# Sheet2.net
KiCad netlist of a schematic drawn in Altium Designer
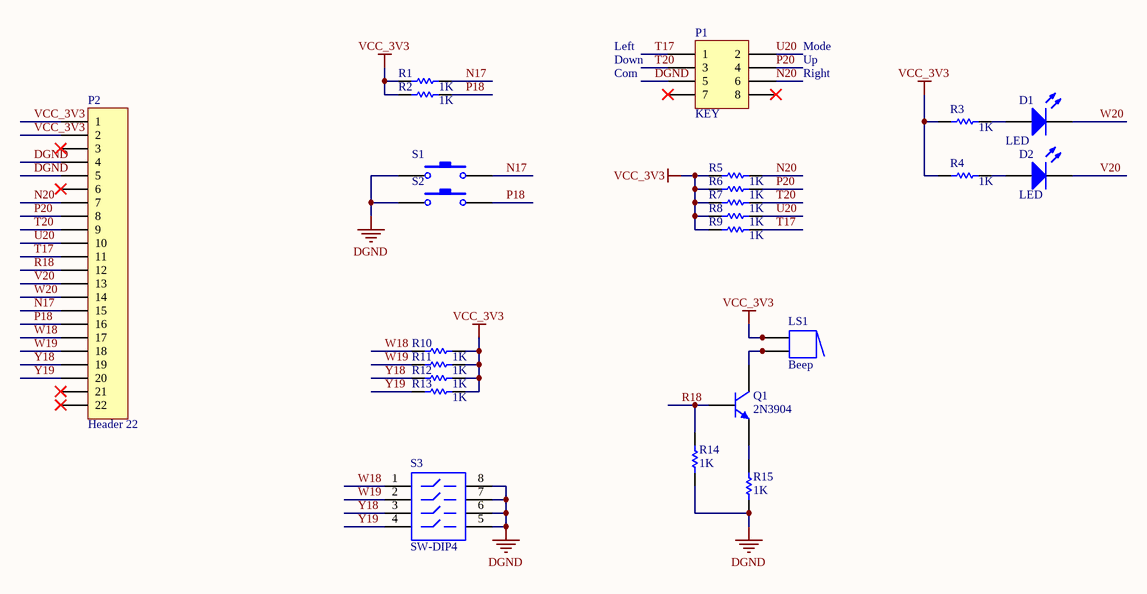
[diagram p0: Sheet2.SchDoc]

(export (version "E")
  (design (tool "Eeschema 10.0.6"))
  (components
    (comp (ref "D1")
      (value "LED")
      (footprint "LED0805绿")
      (description "Typical INFRARED GaAs LED")
      (fields (field (name "PUBLISHER") "Altium Limited"))
      (libsource (lib "Miscellaneous Devices") (part "LED0"))
    )
    (comp (ref "D2")
      (value "LED")
      (footprint "LED0805绿")
      (description "Typical INFRARED GaAs LED")
      (fields (field (name "PUBLISHER") "Altium Limited"))
      (libsource (lib "Miscellaneous Devices") (part "LED0"))
    )
    (comp (ref "LS1")
      (value "Beep")
      (footprint "蜂鸣器")
      (description "Magnetic Transducer Buzzer")
      (fields (field (name "PUBLISHER") "Altium Limited"))
      (libsource (lib "Miscellaneous Devices") (part "Buzzer"))
    )
    (comp (ref "P1")
      (value "KEY")
      (footprint "贴片5向按键")
      (description "Header, 4-Pin, Dual row")
      (fields (field (name "PUBLISHER") "Altium Limited"))
      (libsource (lib "Miscellaneous Connectors") (part "Header 4X2"))
    )
    (comp (ref "P2")
      (value "Header 22")
      (footprint "FPC20Pin")
      (description "Header, 22-Pin")
      (fields (field (name "PUBLISHER") "Altium Limited"))
      (libsource (lib "Miscellaneous Connectors") (part "Header 22"))
    )
    (comp (ref "Q1")
      (value "2N3904")
      (footprint "SOT23")
      (description "NPN General Purpose Amplifier")
      (fields (field (name "PUBLISHER") "Altium Limited"))
      (libsource (lib "Miscellaneous Devices") (part "2N3904"))
    )
    (comp (ref "R1")
      (value "1K")
      (footprint "R0805")
      (description "Resistor")
      (fields (field (name "Comment") "Res1") (field (name "PUBLISHER") "Altium Limited"))
      (libsource (lib "Miscellaneous Devices") (part "Res1"))
    )
    (comp (ref "R2")
      (value "1K")
      (footprint "R0805")
      (description "Resistor")
      (fields (field (name "Comment") "Res1") (field (name "PUBLISHER") "Altium Limited"))
      (libsource (lib "Miscellaneous Devices") (part "Res1"))
    )
    (comp (ref "R3")
      (value "1K")
      (footprint "R0805")
      (description "Resistor")
      (fields (field (name "Comment") "Res1") (field (name "PUBLISHER") "Altium Limited"))
      (libsource (lib "Miscellaneous Devices") (part "Res1"))
    )
    (comp (ref "R4")
      (value "1K")
      (footprint "R0805")
      (description "Resistor")
      (fields (field (name "Comment") "Res1") (field (name "PUBLISHER") "Altium Limited"))
      (libsource (lib "Miscellaneous Devices") (part "Res1"))
    )
    (comp (ref "R5")
      (value "1K")
      (footprint "R0805")
      (description "Resistor")
      (fields (field (name "Comment") "Res1") (field (name "PUBLISHER") "Altium Limited"))
      (libsource (lib "Miscellaneous Devices") (part "Res1"))
    )
    (comp (ref "R6")
      (value "1K")
      (footprint "R0805")
      (description "Resistor")
      (fields (field (name "Comment") "Res1") (field (name "PUBLISHER") "Altium Limited"))
      (libsource (lib "Miscellaneous Devices") (part "Res1"))
    )
    (comp (ref "R7")
      (value "1K")
      (footprint "R0805")
      (description "Resistor")
      (fields (field (name "Comment") "Res1") (field (name "PUBLISHER") "Altium Limited"))
      (libsource (lib "Miscellaneous Devices") (part "Res1"))
    )
    (comp (ref "R8")
      (value "1K")
      (footprint "R0805")
      (description "Resistor")
      (fields (field (name "Comment") "Res1") (field (name "PUBLISHER") "Altium Limited"))
      (libsource (lib "Miscellaneous Devices") (part "Res1"))
    )
    (comp (ref "R9")
      (value "1K")
      (footprint "R0805")
      (description "Resistor")
      (fields (field (name "Comment") "Res1") (field (name "PUBLISHER") "Altium Limited"))
      (libsource (lib "Miscellaneous Devices") (part "Res1"))
    )
    (comp (ref "R10")
      (value "1K")
      (footprint "R0805")
      (description "Resistor")
      (fields (field (name "Comment") "Res1") (field (name "PUBLISHER") "Altium Limited"))
      (libsource (lib "Miscellaneous Devices") (part "Res1"))
    )
    (comp (ref "R11")
      (value "1K")
      (footprint "R0805")
      (description "Resistor")
      (fields (field (name "Comment") "Res1") (field (name "PUBLISHER") "Altium Limited"))
      (libsource (lib "Miscellaneous Devices") (part "Res1"))
    )
    (comp (ref "R12")
      (value "1K")
      (footprint "R0805")
      (description "Resistor")
      (fields (field (name "Comment") "Res1") (field (name "PUBLISHER") "Altium Limited"))
      (libsource (lib "Miscellaneous Devices") (part "Res1"))
    )
    (comp (ref "R13")
      (value "1K")
      (footprint "R0805")
      (description "Resistor")
      (fields (field (name "Comment") "Res1") (field (name "PUBLISHER") "Altium Limited"))
      (libsource (lib "Miscellaneous Devices") (part "Res1"))
    )
    (comp (ref "R14")
      (value "1K")
      (footprint "R0805")
      (description "Resistor")
      (fields (field (name "Comment") "Res1") (field (name "PUBLISHER") "Altium Limited"))
      (libsource (lib "Miscellaneous Devices") (part "Res1"))
    )
    (comp (ref "R15")
      (value "1K")
      (footprint "R0805")
      (description "Resistor")
      (fields (field (name "Comment") "Res1") (field (name "PUBLISHER") "Altium Limited"))
      (libsource (lib "Miscellaneous Devices") (part "Res1"))
    )
    (comp (ref "S1")
      (value "SW-PB")
      (footprint "贴片按键")
      (description "Switch")
      (fields (field (name "PUBLISHER") "Altium Limited"))
      (libsource (lib "Miscellaneous Devices") (part "SW-PB"))
    )
    (comp (ref "S2")
      (value "SW-PB")
      (footprint "贴片按键")
      (description "Switch")
      (fields (field (name "PUBLISHER") "Altium Limited"))
      (libsource (lib "Miscellaneous Devices") (part "SW-PB"))
    )
    (comp (ref "S3")
      (value "SW-DIP4")
      (footprint "拨码开关4")
      (description "DIP Switch")
      (fields (field (name "PUBLISHER") "Altium Limited"))
      (libsource (lib "Miscellaneous Devices") (part "SW-DIP4"))
    )
  )
  (nets
    (net (code "1") (name "/N17") (class "Default")
      (node (ref "P2") (pin "15") (pinfunction "15_15") (pintype "passive"))
      (node (ref "R1") (pin "2") (pinfunction "2_2") (pintype "passive"))
      (node (ref "S1") (pin "2") (pinfunction "2_2") (pintype "passive"))
    )
    (net (code "2") (name "/N20") (class "Default")
      (node (ref "P1") (pin "6") (pinfunction "6_6") (pintype "passive"))
      (node (ref "P2") (pin "7") (pinfunction "7_7") (pintype "passive"))
      (node (ref "R5") (pin "2") (pinfunction "2_2") (pintype "passive"))
    )
    (net (code "3") (name "/P18") (class "Default")
      (node (ref "P2") (pin "16") (pinfunction "16_16") (pintype "passive"))
      (node (ref "R2") (pin "2") (pinfunction "2_2") (pintype "passive"))
      (node (ref "S2") (pin "2") (pinfunction "2_2") (pintype "passive"))
    )
    (net (code "4") (name "/P20") (class "Default")
      (node (ref "P1") (pin "4") (pinfunction "4_4") (pintype "passive"))
      (node (ref "P2") (pin "8") (pinfunction "8_8") (pintype "passive"))
      (node (ref "R6") (pin "2") (pinfunction "2_2") (pintype "passive"))
    )
    (net (code "5") (name "/R18") (class "Default")
      (node (ref "P2") (pin "12") (pinfunction "12_12") (pintype "passive"))
      (node (ref "Q1") (pin "B") (pinfunction "B_B") (pintype "passive"))
      (node (ref "R14") (pin "2") (pinfunction "2_2") (pintype "passive"))
    )
    (net (code "6") (name "/T17") (class "Default")
      (node (ref "P1") (pin "1") (pinfunction "1_1") (pintype "passive"))
      (node (ref "P2") (pin "11") (pinfunction "11_11") (pintype "passive"))
      (node (ref "R9") (pin "2") (pinfunction "2_2") (pintype "passive"))
    )
    (net (code "7") (name "/T20") (class "Default")
      (node (ref "P1") (pin "3") (pinfunction "3_3") (pintype "passive"))
      (node (ref "P2") (pin "9") (pinfunction "9_9") (pintype "passive"))
      (node (ref "R7") (pin "2") (pinfunction "2_2") (pintype "passive"))
    )
    (net (code "8") (name "/U20") (class "Default")
      (node (ref "P1") (pin "2") (pinfunction "2_2") (pintype "passive"))
      (node (ref "P2") (pin "10") (pinfunction "10_10") (pintype "passive"))
      (node (ref "R8") (pin "2") (pinfunction "2_2") (pintype "passive"))
    )
    (net (code "9") (name "/V20") (class "Default")
      (node (ref "D2") (pin "2") (pinfunction "K_2") (pintype "passive"))
      (node (ref "P2") (pin "13") (pinfunction "13_13") (pintype "passive"))
    )
    (net (code "10") (name "/W18") (class "Default")
      (node (ref "P2") (pin "17") (pinfunction "17_17") (pintype "passive"))
      (node (ref "R10") (pin "1") (pinfunction "1_1") (pintype "passive"))
      (node (ref "S3") (pin "1") (pinfunction "1_1") (pintype "passive"))
    )
    (net (code "11") (name "/W19") (class "Default")
      (node (ref "P2") (pin "18") (pinfunction "18_18") (pintype "passive"))
      (node (ref "R11") (pin "1") (pinfunction "1_1") (pintype "passive"))
      (node (ref "S3") (pin "2") (pinfunction "2_2") (pintype "passive"))
    )
    (net (code "12") (name "/W20") (class "Default")
      (node (ref "D1") (pin "2") (pinfunction "K_2") (pintype "passive"))
      (node (ref "P2") (pin "14") (pinfunction "14_14") (pintype "passive"))
    )
    (net (code "13") (name "/Y18") (class "Default")
      (node (ref "P2") (pin "19") (pinfunction "19_19") (pintype "passive"))
      (node (ref "R12") (pin "1") (pinfunction "1_1") (pintype "passive"))
      (node (ref "S3") (pin "3") (pinfunction "3_3") (pintype "passive"))
    )
    (net (code "14") (name "/Y19") (class "Default")
      (node (ref "P2") (pin "20") (pinfunction "20_20") (pintype "passive"))
      (node (ref "R13") (pin "1") (pinfunction "1_1") (pintype "passive"))
      (node (ref "S3") (pin "4") (pinfunction "4_4") (pintype "passive"))
    )
    (net (code "15") (name "DGND") (class "Default")
      (node (ref "P1") (pin "5") (pinfunction "5_5") (pintype "passive"))
      (node (ref "P2") (pin "4") (pinfunction "4_4") (pintype "passive"))
      (node (ref "P2") (pin "5") (pinfunction "5_5") (pintype "passive"))
      (node (ref "R14") (pin "1") (pinfunction "1_1") (pintype "passive"))
      (node (ref "R15") (pin "1") (pinfunction "1_1") (pintype "passive"))
      (node (ref "S1") (pin "1") (pinfunction "1_1") (pintype "passive"))
      (node (ref "S2") (pin "1") (pinfunction "1_1") (pintype "passive"))
      (node (ref "S3") (pin "5") (pinfunction "5_5") (pintype "passive"))
      (node (ref "S3") (pin "6") (pinfunction "6_6") (pintype "passive"))
      (node (ref "S3") (pin "7") (pinfunction "7_7") (pintype "passive"))
      (node (ref "S3") (pin "8") (pinfunction "8_8") (pintype "passive"))
    )
    (net (code "16") (name "Net-(D1-A)") (class "Default")
      (node (ref "D1") (pin "1") (pinfunction "A_1") (pintype "passive"))
      (node (ref "R3") (pin "2") (pinfunction "2_2") (pintype "passive"))
    )
    (net (code "17") (name "Net-(D2-A)") (class "Default")
      (node (ref "D2") (pin "1") (pinfunction "A_1") (pintype "passive"))
      (node (ref "R4") (pin "2") (pinfunction "2_2") (pintype "passive"))
    )
    (net (code "18") (name "Net-(LS1-Pad2)") (class "Default")
      (node (ref "LS1") (pin "2") (pinfunction "2_2") (pintype "passive"))
      (node (ref "Q1") (pin "C") (pinfunction "C_C") (pintype "passive"))
    )
    (net (code "19") (name "Net-(Q1-PadE)") (class "Default")
      (node (ref "Q1") (pin "E") (pinfunction "E_E") (pintype "passive"))
      (node (ref "R15") (pin "2") (pinfunction "2_2") (pintype "passive"))
    )
    (net (code "20") (name "VCC_3V3") (class "Default")
      (node (ref "LS1") (pin "1") (pinfunction "1_1") (pintype "passive"))
      (node (ref "LS1") (pin "1A") (pinfunction "1A_1A") (pintype "passive"))
      (node (ref "P2") (pin "1") (pinfunction "1_1") (pintype "passive"))
      (node (ref "P2") (pin "2") (pinfunction "2_2") (pintype "passive"))
      (node (ref "R1") (pin "1") (pinfunction "1_1") (pintype "passive"))
      (node (ref "R10") (pin "2") (pinfunction "2_2") (pintype "passive"))
      (node (ref "R11") (pin "2") (pinfunction "2_2") (pintype "passive"))
      (node (ref "R12") (pin "2") (pinfunction "2_2") (pintype "passive"))
      (node (ref "R13") (pin "2") (pinfunction "2_2") (pintype "passive"))
      (node (ref "R2") (pin "1") (pinfunction "1_1") (pintype "passive"))
      (node (ref "R3") (pin "1") (pinfunction "1_1") (pintype "passive"))
      (node (ref "R4") (pin "1") (pinfunction "1_1") (pintype "passive"))
      (node (ref "R5") (pin "1") (pinfunction "1_1") (pintype "passive"))
      (node (ref "R6") (pin "1") (pinfunction "1_1") (pintype "passive"))
      (node (ref "R7") (pin "1") (pinfunction "1_1") (pintype "passive"))
      (node (ref "R8") (pin "1") (pinfunction "1_1") (pintype "passive"))
      (node (ref "R9") (pin "1") (pinfunction "1_1") (pintype "passive"))
    )
    (net (code "21") (name "unconnected-(P1-Pad7)") (class "Default")
      (node (ref "P1") (pin "7") (pinfunction "7_7") (pintype "passive+no_connect"))
    )
    (net (code "22") (name "unconnected-(P1-Pad8)") (class "Default")
      (node (ref "P1") (pin "8") (pinfunction "8_8") (pintype "passive+no_connect"))
    )
    (net (code "23") (name "unconnected-(P2-Pad3)") (class "Default")
      (node (ref "P2") (pin "3") (pinfunction "3_3") (pintype "passive+no_connect"))
    )
    (net (code "24") (name "unconnected-(P2-Pad6)") (class "Default")
      (node (ref "P2") (pin "6") (pinfunction "6_6") (pintype "passive+no_connect"))
    )
    (net (code "25") (name "unconnected-(P2-Pad21)") (class "Default")
      (node (ref "P2") (pin "21") (pinfunction "21_21") (pintype "passive+no_connect"))
    )
    (net (code "26") (name "unconnected-(P2-Pad22)") (class "Default")
      (node (ref "P2") (pin "22") (pinfunction "22_22") (pintype "passive+no_connect"))
    )
  )
)
